# LED_ChaserSch.net
KiCad netlist of a schematic drawn in Altium Designer
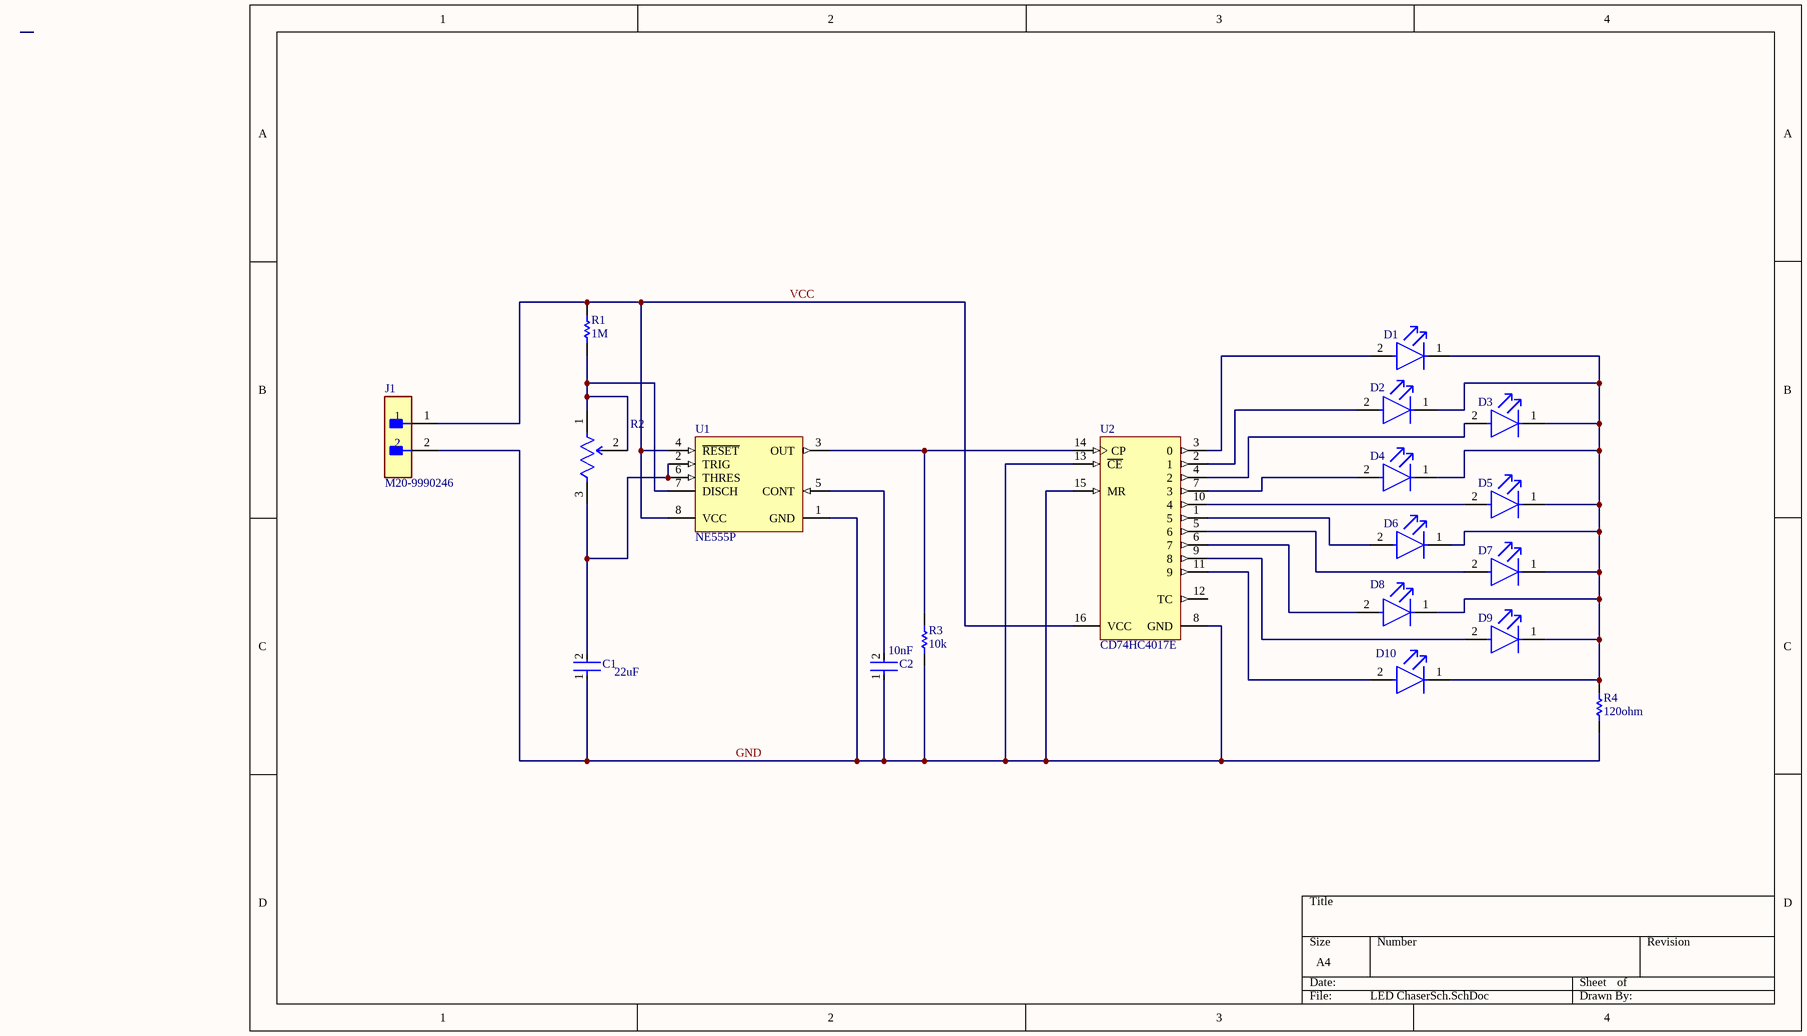
[diagram p0: LED ChaserSch.SchDoc]

(export (version "E")
  (design (tool "Eeschema 10.0.6"))
  (components
    (comp (ref "C1")
      (value "RCER71E106K3DBH03A")
      (footprint "FP-RCE3DB-MFG")
      (description "Cap Ceramic 10uF 25V X7R ±10% Radial 2.5mm +125°C Automotive Ammo Pack")
      (fields (field (name "TOLERANCE") "10%") (field (name "CAPACITANCE") "22uF"))
      (libsource (lib "Altium Content Vault") (part "b4654b650e69147ec39a6b967a45e02"))
    )
    (comp (ref "C2")
      (value "RCER71E106K3DBH03A")
      (footprint "FP-RCE3DB-MFG")
      (description "Cap Ceramic 10uF 25V X7R ±10% Radial 2.5mm +125°C Automotive Ammo Pack")
      (fields (field (name "TOLERANCE") "10%") (field (name "CAPACITANCE") "10nF"))
      (libsource (lib "Altium Content Vault") (part "b4654b650e69147ec39a6b967a45e02"))
    )
    (comp (ref "D1")
      (value "LTST-C190GKT")
      (footprint "FP-LTST-C190GKT-MFG")
      (description "LED GREEN CLEAR CHIP SMD")
      (fields (field (name "VOLTAGE") "2V"))
      (libsource (lib "Altium Content Vault") (part "8706943c75ba83719d021d2fdc84c58"))
    )
    (comp (ref "D2")
      (value "LTST-C190GKT")
      (footprint "FP-LTST-C190GKT-MFG")
      (description "LED GREEN CLEAR CHIP SMD")
      (fields (field (name "VOLTAGE") "2V"))
      (libsource (lib "Altium Content Vault") (part "8706943c75ba83719d021d2fdc84c58"))
    )
    (comp (ref "D3")
      (value "LTST-C190GKT")
      (footprint "FP-LTST-C190GKT-MFG")
      (description "LED GREEN CLEAR CHIP SMD")
      (fields (field (name "VOLTAGE") "2V"))
      (libsource (lib "Altium Content Vault") (part "8706943c75ba83719d021d2fdc84c58"))
    )
    (comp (ref "D4")
      (value "LTST-C190GKT")
      (footprint "FP-LTST-C190GKT-MFG")
      (description "LED GREEN CLEAR CHIP SMD")
      (fields (field (name "VOLTAGE") "2V"))
      (libsource (lib "Altium Content Vault") (part "8706943c75ba83719d021d2fdc84c58"))
    )
    (comp (ref "D5")
      (value "LTST-C190GKT")
      (footprint "FP-LTST-C190GKT-MFG")
      (description "LED GREEN CLEAR CHIP SMD")
      (fields (field (name "VOLTAGE") "2V"))
      (libsource (lib "Altium Content Vault") (part "8706943c75ba83719d021d2fdc84c58"))
    )
    (comp (ref "D6")
      (value "LTST-C190GKT")
      (footprint "FP-LTST-C190GKT-MFG")
      (description "LED GREEN CLEAR CHIP SMD")
      (fields (field (name "VOLTAGE") "2V"))
      (libsource (lib "Altium Content Vault") (part "8706943c75ba83719d021d2fdc84c58"))
    )
    (comp (ref "D7")
      (value "LTST-C190GKT")
      (footprint "FP-LTST-C190GKT-MFG")
      (description "LED GREEN CLEAR CHIP SMD")
      (fields (field (name "VOLTAGE") "2V"))
      (libsource (lib "Altium Content Vault") (part "8706943c75ba83719d021d2fdc84c58"))
    )
    (comp (ref "D8")
      (value "LTST-C190GKT")
      (footprint "FP-LTST-C190GKT-MFG")
      (description "LED GREEN CLEAR CHIP SMD")
      (fields (field (name "VOLTAGE") "2V"))
      (libsource (lib "Altium Content Vault") (part "8706943c75ba83719d021d2fdc84c58"))
    )
    (comp (ref "D9")
      (value "LTST-C190GKT")
      (footprint "FP-LTST-C190GKT-MFG")
      (description "LED GREEN CLEAR CHIP SMD")
      (fields (field (name "VOLTAGE") "2V"))
      (libsource (lib "Altium Content Vault") (part "8706943c75ba83719d021d2fdc84c58"))
    )
    (comp (ref "D10")
      (value "LTST-C190GKT")
      (footprint "FP-LTST-C190GKT-MFG")
      (description "LED GREEN CLEAR CHIP SMD")
      (fields (field (name "VOLTAGE") "2V"))
      (libsource (lib "Altium Content Vault") (part "8706943c75ba83719d021d2fdc84c58"))
    )
    (comp (ref "J1")
      (value "M20-9990246")
      (footprint "FP-M20-9990246-MFG")
      (description "Connector Header Through Hole 2 position 0.100\" (2.54mm)")
      (fields (field (name "OCTOPART") "https://octopart.com/m20-9990246-harwin-2590635"))
      (libsource (lib "Altium Content Vault") (part "3bc925449376181038e59eaffc5286c"))
    )
    (comp (ref "R1")
      (value "1M")
      (footprint "OMTE-RES7X2.5-2")
      (fields
        (field (name "TOLERANCE") "±5%")
        (field (name "PARTNUMBER") "OD103JE")
        (field (name "MANUFACTURER") "Ohmite")
      )
      (libsource (lib "Altium Content Vault") (part "RES-2"))
    )
    (comp (ref "R2")
      (value "3312J-1-504E")
      (footprint "FP-3312-MFG")
      (description "TRIMMER 500K OHM 0.1W J LEAD TOP")
      (fields (field (name "TOLERANCE") "20%"))
      (libsource (lib "Altium Content Vault") (part "13357d81287629c2fd191d242cfa50c"))
    )
    (comp (ref "R3")
      (value "10k")
      (footprint "OMTE-RES7X2.5-2")
      (fields
        (field (name "TOLERANCE") "±5%")
        (field (name "PARTNUMBER") "OD103JE")
        (field (name "MANUFACTURER") "Ohmite")
      )
      (libsource (lib "Altium Content Vault") (part "RES-2"))
    )
    (comp (ref "R4")
      (value "120ohm")
      (footprint "OMTE-RES7X2.5-2")
      (fields
        (field (name "TOLERANCE") "±5%")
        (field (name "PARTNUMBER") "OD103JE")
        (field (name "MANUFACTURER") "Ohmite")
      )
      (libsource (lib "Altium Content Vault") (part "RES-2"))
    )
    (comp (ref "U1")
      (value "NE555P")
      (footprint "P0008A")
      (description "Precision Timer, 4.5 to 16 V, 0 to 70 degC, 8-Pin DIP, Pb-Free, Tube")
      (fields (field (name "MANUFACTURER") "TexasInstruments"))
      (libsource (lib "Altium Content Vault") (part "TI-NE555-P8"))
    )
    (comp (ref "U2")
      (value "CD74HC4017E")
      (footprint "N0016A")
      (description "High Speed CMOS Logic Decade Counter/Divider with 10 Decoded Outputs, N0016A, TUBE")
      (fields
        (field (name "GENERIC PART NUMBER") "CD74HC4017")
        (field (name "MANUFACTURER") "Texas Instruments")
      )
      (libsource (lib "Altium Content Vault") (part "TI-CD74HC4017-16"))
    )
  )
  (nets
    (net (code "1") (name "/GND") (class "Default")
      (node (ref "C1") (pin "1") (pinfunction "1_1") (pintype "passive"))
      (node (ref "C2") (pin "1") (pinfunction "1_1") (pintype "passive"))
      (node (ref "J1") (pin "2") (pinfunction "2_2") (pintype "passive"))
      (node (ref "R3") (pin "1") (pinfunction "1_1") (pintype "passive"))
      (node (ref "R4") (pin "1") (pinfunction "1_1") (pintype "passive"))
      (node (ref "U1") (pin "1") (pinfunction "GND_1") (pintype "power_in"))
      (node (ref "U2") (pin "13") (pinfunction "~{CE}_13") (pintype "input"))
      (node (ref "U2") (pin "15") (pinfunction "MR_15") (pintype "input"))
      (node (ref "U2") (pin "8") (pinfunction "GND_8") (pintype "power_in"))
    )
    (net (code "2") (name "/VCC") (class "Default")
      (node (ref "J1") (pin "1") (pinfunction "1_1") (pintype "passive"))
      (node (ref "R1") (pin "2") (pinfunction "2_2") (pintype "passive"))
      (node (ref "U1") (pin "4") (pinfunction "~{RESET}_4") (pintype "input"))
      (node (ref "U1") (pin "8") (pinfunction "VCC_8") (pintype "power_in"))
      (node (ref "U2") (pin "16") (pinfunction "VCC_16") (pintype "power_in"))
    )
    (net (code "3") (name "Net-(D1-A)") (class "Default")
      (node (ref "D1") (pin "2") (pinfunction "A_2") (pintype "passive"))
      (node (ref "U2") (pin "3") (pinfunction "0_3") (pintype "output"))
    )
    (net (code "4") (name "Net-(D1-C)") (class "Default")
      (node (ref "D1") (pin "1") (pinfunction "C_1") (pintype "passive"))
      (node (ref "D10") (pin "1") (pinfunction "C_1") (pintype "passive"))
      (node (ref "D2") (pin "1") (pinfunction "C_1") (pintype "passive"))
      (node (ref "D3") (pin "1") (pinfunction "C_1") (pintype "passive"))
      (node (ref "D4") (pin "1") (pinfunction "C_1") (pintype "passive"))
      (node (ref "D5") (pin "1") (pinfunction "C_1") (pintype "passive"))
      (node (ref "D6") (pin "1") (pinfunction "C_1") (pintype "passive"))
      (node (ref "D7") (pin "1") (pinfunction "C_1") (pintype "passive"))
      (node (ref "D8") (pin "1") (pinfunction "C_1") (pintype "passive"))
      (node (ref "D9") (pin "1") (pinfunction "C_1") (pintype "passive"))
      (node (ref "R4") (pin "2") (pinfunction "2_2") (pintype "passive"))
    )
    (net (code "5") (name "Net-(D2-A)") (class "Default")
      (node (ref "D2") (pin "2") (pinfunction "A_2") (pintype "passive"))
      (node (ref "U2") (pin "2") (pinfunction "1_2") (pintype "output"))
    )
    (net (code "6") (name "Net-(D3-A)") (class "Default")
      (node (ref "D3") (pin "2") (pinfunction "A_2") (pintype "passive"))
      (node (ref "U2") (pin "4") (pinfunction "2_4") (pintype "output"))
    )
    (net (code "7") (name "Net-(D4-A)") (class "Default")
      (node (ref "D4") (pin "2") (pinfunction "A_2") (pintype "passive"))
      (node (ref "U2") (pin "7") (pinfunction "3_7") (pintype "output"))
    )
    (net (code "8") (name "Net-(D5-A)") (class "Default")
      (node (ref "D5") (pin "2") (pinfunction "A_2") (pintype "passive"))
      (node (ref "U2") (pin "10") (pinfunction "4_10") (pintype "output"))
    )
    (net (code "9") (name "Net-(D6-A)") (class "Default")
      (node (ref "D6") (pin "2") (pinfunction "A_2") (pintype "passive"))
      (node (ref "U2") (pin "1") (pinfunction "5_1") (pintype "output"))
    )
    (net (code "10") (name "Net-(D7-A)") (class "Default")
      (node (ref "D7") (pin "2") (pinfunction "A_2") (pintype "passive"))
      (node (ref "U2") (pin "5") (pinfunction "6_5") (pintype "output"))
    )
    (net (code "11") (name "Net-(D8-A)") (class "Default")
      (node (ref "D8") (pin "2") (pinfunction "A_2") (pintype "passive"))
      (node (ref "U2") (pin "6") (pinfunction "7_6") (pintype "output"))
    )
    (net (code "12") (name "Net-(D9-A)") (class "Default")
      (node (ref "D9") (pin "2") (pinfunction "A_2") (pintype "passive"))
      (node (ref "U2") (pin "9") (pinfunction "8_9") (pintype "output"))
    )
    (net (code "13") (name "Net-(D10-A)") (class "Default")
      (node (ref "D10") (pin "2") (pinfunction "A_2") (pintype "passive"))
      (node (ref "U2") (pin "11") (pinfunction "9_11") (pintype "output"))
    )
    (net (code "14") (name "Net-(R2-CCW)") (class "Default")
      (node (ref "R1") (pin "1") (pinfunction "1_1") (pintype "passive"))
      (node (ref "R2") (pin "1") (pinfunction "CCW_1") (pintype "passive"))
      (node (ref "R2") (pin "2") (pinfunction "WIPER_2") (pintype "passive"))
      (node (ref "U1") (pin "7") (pinfunction "DISCH_7") (pintype "open_collector"))
    )
    (net (code "15") (name "Net-(R2-CW)") (class "Default")
      (node (ref "C1") (pin "2") (pinfunction "2_2") (pintype "passive"))
      (node (ref "R2") (pin "3") (pinfunction "CW_3") (pintype "passive"))
      (node (ref "U1") (pin "2") (pinfunction "TRIG_2") (pintype "input"))
      (node (ref "U1") (pin "6") (pinfunction "THRES_6") (pintype "input"))
    )
    (net (code "16") (name "Net-(U1-CONT)") (class "Default")
      (node (ref "C2") (pin "2") (pinfunction "2_2") (pintype "passive"))
      (node (ref "U1") (pin "5") (pinfunction "CONT_5") (pintype "input"))
    )
    (net (code "17") (name "Net-(U1-OUT)") (class "Default")
      (node (ref "R3") (pin "2") (pinfunction "2_2") (pintype "passive"))
      (node (ref "U1") (pin "3") (pinfunction "OUT_3") (pintype "output"))
      (node (ref "U2") (pin "14") (pinfunction "CP_14") (pintype "input"))
    )
    (net (code "18") (name "unconnected-(U2-TC-Pad12)") (class "Default")
      (node (ref "U2") (pin "12") (pinfunction "TC_12") (pintype "output"))
    )
  )
)
